# MS-PS3.net
KiCad netlist of a schematic drawn in EAGLE
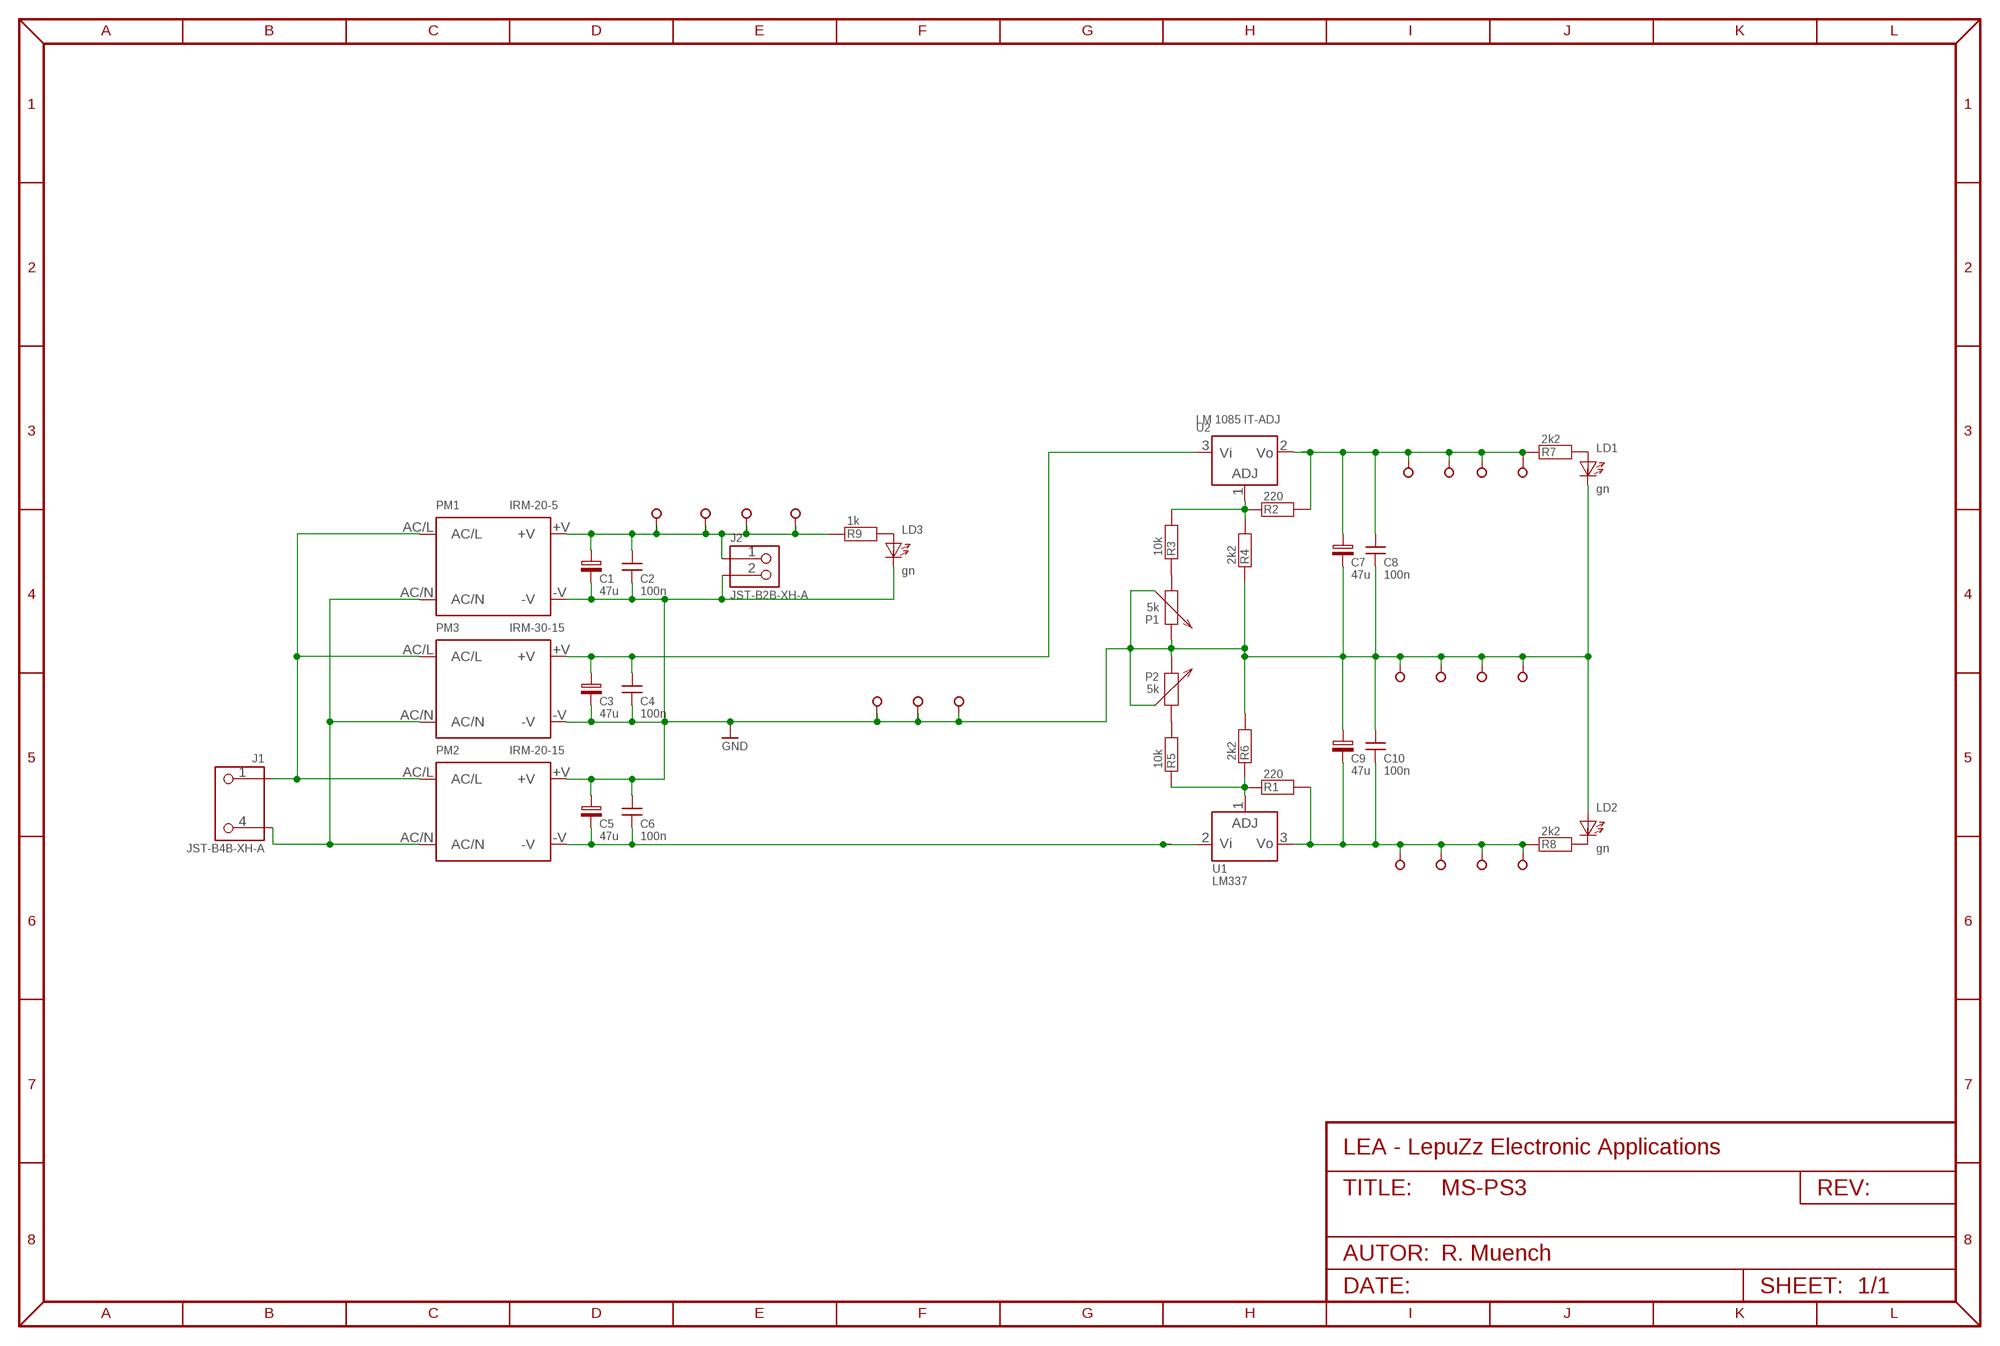
[diagram p0: schematic, sheet 1]

(export (version "E")
  (design (tool "Eeschema 10.0.6"))
  (components
    (comp (ref "C1")
      (value "47u")
      (footprint "eagle-import:ES2,5X6,3")
      (libsource (lib "eagle-import") (part "C-ELKO_2,5X6,3_R"))
    )
    (comp (ref "C2")
      (value "100n")
      (footprint "eagle-import:K5-2,5")
      (libsource (lib "eagle-import") (part "C_K_5X2.5"))
    )
    (comp (ref "C3")
      (value "47u")
      (footprint "eagle-import:ES2,5X6,3")
      (libsource (lib "eagle-import") (part "C-ELKO_2,5X6,3_R"))
    )
    (comp (ref "C4")
      (value "100n")
      (footprint "eagle-import:K5-2,5")
      (libsource (lib "eagle-import") (part "C_K_5X2.5"))
    )
    (comp (ref "C5")
      (value "47u")
      (footprint "eagle-import:ES2,5X6,3")
      (libsource (lib "eagle-import") (part "C-ELKO_2,5X6,3_R"))
    )
    (comp (ref "C6")
      (value "100n")
      (footprint "eagle-import:K5-2,5")
      (libsource (lib "eagle-import") (part "C_K_5X2.5"))
    )
    (comp (ref "C7")
      (value "47u")
      (footprint "eagle-import:ES2,5X6,3")
      (libsource (lib "eagle-import") (part "C-ELKO_2,5X6,3_R"))
    )
    (comp (ref "C8")
      (value "100n")
      (footprint "eagle-import:K5-2,5")
      (libsource (lib "eagle-import") (part "C_K_5X2.5"))
    )
    (comp (ref "C9")
      (value "47u")
      (footprint "eagle-import:ES2,5X6,3")
      (libsource (lib "eagle-import") (part "C-ELKO_2,5X6,3_R"))
    )
    (comp (ref "C10")
      (value "100n")
      (footprint "eagle-import:K5-2,5")
      (libsource (lib "eagle-import") (part "C_K_5X2.5"))
    )
    (comp (ref "J1")
      (value "JST-B4B-XH-A")
      (footprint "eagle-import:JST-B4B-XH-A-HV")
      (libsource (lib "eagle-import") (part "CON04"))
    )
    (comp (ref "J2")
      (value "JST-B2B-XH-A")
      (footprint "eagle-import:JST-B2B-XH-A")
      (libsource (lib "eagle-import") (part "CON02XH-B2B"))
    )
    (comp (ref "J3")
      (value "FLACHSTECKER-6,35")
      (footprint "eagle-import:FLACHSTECKER-6,35")
      (libsource (lib "eagle-import") (part "FLACHSTECKER-6,35"))
    )
    (comp (ref "J4")
      (value "FLACHSTECKER-6,35")
      (footprint "eagle-import:FLACHSTECKER-6,35")
      (libsource (lib "eagle-import") (part "FLACHSTECKER-6,35"))
    )
    (comp (ref "J5")
      (value "FLACHSTECKER-6,35")
      (footprint "eagle-import:FLACHSTECKER-6,35")
      (libsource (lib "eagle-import") (part "FLACHSTECKER-6,35"))
    )
    (comp (ref "J6")
      (value "FLACHSTECKER-6,35")
      (footprint "eagle-import:FLACHSTECKER-6,35")
      (libsource (lib "eagle-import") (part "FLACHSTECKER-6,35"))
    )
    (comp (ref "J7")
      (value "FLACHSTECKER-6,35")
      (footprint "eagle-import:FLACHSTECKER-6,35")
      (libsource (lib "eagle-import") (part "FLACHSTECKER-6,35"))
    )
    (comp (ref "J8")
      (value "FLACHSTECKER-6,35")
      (footprint "eagle-import:FLACHSTECKER-6,35")
      (libsource (lib "eagle-import") (part "FLACHSTECKER-6,35"))
    )
    (comp (ref "J9")
      (value "FLACHSTECKER-6,35")
      (footprint "eagle-import:FLACHSTECKER-6,35")
      (libsource (lib "eagle-import") (part "FLACHSTECKER-6,35"))
    )
    (comp (ref "J10")
      (value "FLACHSTECKER-6,35")
      (footprint "eagle-import:FLACHSTECKER-6,35")
      (libsource (lib "eagle-import") (part "FLACHSTECKER-6,35"))
    )
    (comp (ref "J11")
      (value "FLACHSTECKER-6,35")
      (footprint "eagle-import:FLACHSTECKER-6,35")
      (libsource (lib "eagle-import") (part "FLACHSTECKER-6,35"))
    )
    (comp (ref "J12")
      (value "FLACHSTECKER-6,35")
      (footprint "eagle-import:FLACHSTECKER-6,35")
      (libsource (lib "eagle-import") (part "FLACHSTECKER-6,35"))
    )
    (comp (ref "J13")
      (value "FLACHSTECKER-6,35")
      (footprint "eagle-import:FLACHSTECKER-6,35")
      (libsource (lib "eagle-import") (part "FLACHSTECKER-6,35"))
    )
    (comp (ref "J14")
      (value "FLACHSTECKER-6,35")
      (footprint "eagle-import:FLACHSTECKER-6,35")
      (libsource (lib "eagle-import") (part "FLACHSTECKER-6,35"))
    )
    (comp (ref "J15")
      (value "FLACHSTECKER-6,35")
      (footprint "eagle-import:FLACHSTECKER-6,35")
      (libsource (lib "eagle-import") (part "FLACHSTECKER-6,35"))
    )
    (comp (ref "J16")
      (value "FLACHSTECKER-6,35")
      (footprint "eagle-import:FLACHSTECKER-6,35")
      (libsource (lib "eagle-import") (part "FLACHSTECKER-6,35"))
    )
    (comp (ref "J17")
      (value "FLACHSTECKER-6,35")
      (footprint "eagle-import:FLACHSTECKER-6,35")
      (libsource (lib "eagle-import") (part "FLACHSTECKER-6,35"))
    )
    (comp (ref "J18")
      (value "FLACHSTECKER-6,35")
      (footprint "eagle-import:FLACHSTECKER-6,35")
      (libsource (lib "eagle-import") (part "FLACHSTECKER-6,35"))
    )
    (comp (ref "J19")
      (value "FLACHSTECKER-6,35")
      (footprint "eagle-import:FLACHSTECKER-6,35")
      (libsource (lib "eagle-import") (part "FLACHSTECKER-6,35"))
    )
    (comp (ref "J20")
      (value "FLACHSTECKER-6,35")
      (footprint "eagle-import:FLACHSTECKER-6,35")
      (libsource (lib "eagle-import") (part "FLACHSTECKER-6,35"))
    )
    (comp (ref "J21")
      (value "FLACHSTECKER-6,35")
      (footprint "eagle-import:FLACHSTECKER-6,35")
      (libsource (lib "eagle-import") (part "FLACHSTECKER-6,35"))
    )
    (comp (ref "LD1")
      (value "gn")
      (footprint "eagle-import:LED3")
      (libsource (lib "eagle-import") (part "LED3MM"))
    )
    (comp (ref "LD2")
      (value "gn")
      (footprint "eagle-import:LED3")
      (libsource (lib "eagle-import") (part "LED3MM"))
    )
    (comp (ref "LD3")
      (value "gn")
      (footprint "eagle-import:LED3")
      (libsource (lib "eagle-import") (part "LED3MM"))
    )
    (comp (ref "P1")
      (value "5k")
      (footprint "eagle-import:POT-25-64Y")
      (libsource (lib "eagle-import") (part "R-TRIM64Y"))
    )
    (comp (ref "P2")
      (value "5k")
      (footprint "eagle-import:POT-25-64Y")
      (libsource (lib "eagle-import") (part "R-TRIM64Y"))
    )
    (comp (ref "PM1")
      (value "IRM-20-5")
      (footprint "eagle-import:IRM-20")
      (libsource (lib "eagle-import") (part "IRM-XX20WATT"))
    )
    (comp (ref "PM2")
      (value "IRM-20-15")
      (footprint "eagle-import:IRM-20")
      (libsource (lib "eagle-import") (part "IRM-XX20WATT"))
    )
    (comp (ref "PM3")
      (value "IRM-30-15")
      (footprint "eagle-import:IRM-30")
      (libsource (lib "eagle-import") (part "IRM-XX30WATT"))
    )
    (comp (ref "R1")
      (value "220")
      (footprint "eagle-import:R-7,5")
      (libsource (lib "eagle-import") (part "R_7.5_250"))
    )
    (comp (ref "R2")
      (value "220")
      (footprint "eagle-import:R-7,5")
      (libsource (lib "eagle-import") (part "R_7.5_250"))
    )
    (comp (ref "R3")
      (value "10k")
      (footprint "eagle-import:R-7,5")
      (libsource (lib "eagle-import") (part "R_7.5_250"))
    )
    (comp (ref "R4")
      (value "2k2")
      (footprint "eagle-import:R-7,5")
      (libsource (lib "eagle-import") (part "R_7.5_250"))
    )
    (comp (ref "R5")
      (value "10k")
      (footprint "eagle-import:R-7,5")
      (libsource (lib "eagle-import") (part "R_7.5_250"))
    )
    (comp (ref "R6")
      (value "2k2")
      (footprint "eagle-import:R-7,5")
      (libsource (lib "eagle-import") (part "R_7.5_250"))
    )
    (comp (ref "R7")
      (value "2k2")
      (footprint "eagle-import:R-7,5")
      (libsource (lib "eagle-import") (part "R_7.5_250"))
    )
    (comp (ref "R8")
      (value "2k2")
      (footprint "eagle-import:R-7,5")
      (libsource (lib "eagle-import") (part "R_7.5_250"))
    )
    (comp (ref "R9")
      (value "1k")
      (footprint "eagle-import:R-7,5")
      (libsource (lib "eagle-import") (part "R_7.5_250"))
    )
    (comp (ref "U$5")
      (value "SK65")
      (footprint "eagle-import:SK65-37,5")
      (libsource (lib "eagle-import") (part "SK65"))
    )
    (comp (ref "U$7")
      (value "SK65")
      (footprint "eagle-import:SK65-37,5")
      (libsource (lib "eagle-import") (part "SK65"))
    )
    (comp (ref "U1")
      (value "LM337")
      (footprint "eagle-import:TO-220N")
      (libsource (lib "eagle-import") (part "337TA"))
    )
    (comp (ref "U2")
      (value "LM 1085 IT-ADJ")
      (footprint "eagle-import:TO-220N")
      (libsource (lib "eagle-import") (part "317TN"))
    )
  )
  (nets
    (net (code "1") (name "GND") (class "Default")
      (node (ref "C1") (pin "2") (pinfunction "2_2") (pintype "passive"))
      (node (ref "C10") (pin "1") (pinfunction "1_1") (pintype "passive"))
      (node (ref "C2") (pin "2") (pinfunction "2_2") (pintype "passive"))
      (node (ref "C3") (pin "2") (pinfunction "2_2") (pintype "passive"))
      (node (ref "C4") (pin "2") (pinfunction "2_2") (pintype "passive"))
      (node (ref "C5") (pin "1") (pinfunction "1_1") (pintype "passive"))
      (node (ref "C6") (pin "1") (pinfunction "1_1") (pintype "passive"))
      (node (ref "C7") (pin "2") (pinfunction "2_2") (pintype "passive"))
      (node (ref "C8") (pin "2") (pinfunction "2_2") (pintype "passive"))
      (node (ref "C9") (pin "1") (pinfunction "1_1") (pintype "passive"))
      (node (ref "J13") (pin "P$1") (pinfunction "P$1_P$1") (pintype "bidirectional"))
      (node (ref "J13") (pin "P$2") (pinfunction "P$2_P$2") (pintype "bidirectional"))
      (node (ref "J14") (pin "P$1") (pinfunction "P$1_P$1") (pintype "bidirectional"))
      (node (ref "J14") (pin "P$2") (pinfunction "P$2_P$2") (pintype "bidirectional"))
      (node (ref "J15") (pin "P$1") (pinfunction "P$1_P$1") (pintype "bidirectional"))
      (node (ref "J15") (pin "P$2") (pinfunction "P$2_P$2") (pintype "bidirectional"))
      (node (ref "J16") (pin "P$1") (pinfunction "P$1_P$1") (pintype "bidirectional"))
      (node (ref "J16") (pin "P$2") (pinfunction "P$2_P$2") (pintype "bidirectional"))
      (node (ref "J2") (pin "2") (pinfunction "2_2") (pintype "passive"))
      (node (ref "J21") (pin "P$1") (pinfunction "P$1_P$1") (pintype "bidirectional"))
      (node (ref "J21") (pin "P$2") (pinfunction "P$2_P$2") (pintype "bidirectional"))
      (node (ref "J7") (pin "P$1") (pinfunction "P$1_P$1") (pintype "bidirectional"))
      (node (ref "J7") (pin "P$2") (pinfunction "P$2_P$2") (pintype "bidirectional"))
      (node (ref "J8") (pin "P$1") (pinfunction "P$1_P$1") (pintype "bidirectional"))
      (node (ref "J8") (pin "P$2") (pinfunction "P$2_P$2") (pintype "bidirectional"))
      (node (ref "LD1") (pin "K") (pinfunction "K_K") (pintype "passive"))
      (node (ref "LD2") (pin "A") (pinfunction "A_A") (pintype "passive"))
      (node (ref "LD3") (pin "K") (pinfunction "K_K") (pintype "passive"))
      (node (ref "P1") (pin "2") (pinfunction "2_2") (pintype "passive"))
      (node (ref "P1") (pin "3") (pinfunction "3_3") (pintype "passive"))
      (node (ref "P2") (pin "2") (pinfunction "2_2") (pintype "passive"))
      (node (ref "P2") (pin "3") (pinfunction "3_3") (pintype "passive"))
      (node (ref "PM1") (pin "-V") (pinfunction "-V_-V") (pintype "passive"))
      (node (ref "PM2") (pin "+V") (pinfunction "+V_+V") (pintype "passive"))
      (node (ref "PM3") (pin "-V") (pinfunction "-V_-V") (pintype "passive"))
      (node (ref "R4") (pin "1") (pinfunction "1_1") (pintype "passive"))
      (node (ref "R6") (pin "2") (pinfunction "2_2") (pintype "passive"))
    )
    (net (code "2") (name "Net-(C1-Pad1)") (class "Default")
      (node (ref "C1") (pin "1") (pinfunction "1_1") (pintype "passive"))
      (node (ref "C2") (pin "1") (pinfunction "1_1") (pintype "passive"))
      (node (ref "J2") (pin "1") (pinfunction "1_1") (pintype "passive"))
      (node (ref "J3") (pin "P$1") (pinfunction "P$1_P$1") (pintype "bidirectional"))
      (node (ref "J3") (pin "P$2") (pinfunction "P$2_P$2") (pintype "bidirectional"))
      (node (ref "J4") (pin "P$1") (pinfunction "P$1_P$1") (pintype "bidirectional"))
      (node (ref "J4") (pin "P$2") (pinfunction "P$2_P$2") (pintype "bidirectional"))
      (node (ref "J5") (pin "P$1") (pinfunction "P$1_P$1") (pintype "bidirectional"))
      (node (ref "J5") (pin "P$2") (pinfunction "P$2_P$2") (pintype "bidirectional"))
      (node (ref "J6") (pin "P$1") (pinfunction "P$1_P$1") (pintype "bidirectional"))
      (node (ref "J6") (pin "P$2") (pinfunction "P$2_P$2") (pintype "bidirectional"))
      (node (ref "PM1") (pin "+V") (pinfunction "+V_+V") (pintype "passive"))
      (node (ref "R9") (pin "1") (pinfunction "1_1") (pintype "passive"))
    )
    (net (code "3") (name "Net-(J1-Pad1)") (class "Default")
      (node (ref "J1") (pin "1") (pinfunction "1_1") (pintype "passive"))
      (node (ref "PM1") (pin "AC/L") (pinfunction "AC/L_AC/L") (pintype "passive"))
      (node (ref "PM2") (pin "AC/L") (pinfunction "AC/L_AC/L") (pintype "passive"))
      (node (ref "PM3") (pin "AC/L") (pinfunction "AC/L_AC/L") (pintype "passive"))
    )
    (net (code "4") (name "Net-(J1-Pad4)") (class "Default")
      (node (ref "J1") (pin "4") (pinfunction "4_4") (pintype "passive"))
      (node (ref "PM1") (pin "AC/N") (pinfunction "AC/N_AC/N") (pintype "passive"))
      (node (ref "PM2") (pin "AC/N") (pinfunction "AC/N_AC/N") (pintype "passive"))
      (node (ref "PM3") (pin "AC/N") (pinfunction "AC/N_AC/N") (pintype "passive"))
    )
    (net (code "5") (name "Net-(LD1-PadA)") (class "Default")
      (node (ref "LD1") (pin "A") (pinfunction "A_A") (pintype "passive"))
      (node (ref "R7") (pin "2") (pinfunction "2_2") (pintype "passive"))
    )
    (net (code "6") (name "Net-(LD2-PadK)") (class "Default")
      (node (ref "LD2") (pin "K") (pinfunction "K_K") (pintype "passive"))
      (node (ref "R8") (pin "2") (pinfunction "2_2") (pintype "passive"))
    )
    (net (code "7") (name "Net-(LD3-PadA)") (class "Default")
      (node (ref "LD3") (pin "A") (pinfunction "A_A") (pintype "passive"))
      (node (ref "R9") (pin "2") (pinfunction "2_2") (pintype "passive"))
    )
    (net (code "8") (name "Net-(P1-Pad1)") (class "Default")
      (node (ref "P1") (pin "1") (pinfunction "1_1") (pintype "passive"))
      (node (ref "R3") (pin "1") (pinfunction "1_1") (pintype "passive"))
    )
    (net (code "9") (name "Net-(P2-Pad1)") (class "Default")
      (node (ref "P2") (pin "1") (pinfunction "1_1") (pintype "passive"))
      (node (ref "R5") (pin "2") (pinfunction "2_2") (pintype "passive"))
    )
    (net (code "10") (name "Net-(U1-ADJ)") (class "Default")
      (node (ref "R1") (pin "1") (pinfunction "1_1") (pintype "passive"))
      (node (ref "R5") (pin "1") (pinfunction "1_1") (pintype "passive"))
      (node (ref "R6") (pin "1") (pinfunction "1_1") (pintype "passive"))
      (node (ref "U1") (pin "1") (pinfunction "ADJ_1") (pintype "input"))
    )
    (net (code "11") (name "Net-(U1-VI)") (class "Default")
      (node (ref "C5") (pin "2") (pinfunction "2_2") (pintype "passive"))
      (node (ref "C6") (pin "2") (pinfunction "2_2") (pintype "passive"))
      (node (ref "PM2") (pin "-V") (pinfunction "-V_-V") (pintype "passive"))
      (node (ref "U$5") (pin "P$1") (pinfunction "P$1_P$1") (pintype "bidirectional"))
      (node (ref "U$5") (pin "P$2") (pinfunction "P$2_P$2") (pintype "bidirectional"))
      (node (ref "U1") (pin "2") (pinfunction "VI_2") (pintype "input"))
    )
    (net (code "12") (name "Net-(U1-VO)") (class "Default")
      (node (ref "C10") (pin "2") (pinfunction "2_2") (pintype "passive"))
      (node (ref "C9") (pin "2") (pinfunction "2_2") (pintype "passive"))
      (node (ref "J17") (pin "P$1") (pinfunction "P$1_P$1") (pintype "bidirectional"))
      (node (ref "J17") (pin "P$2") (pinfunction "P$2_P$2") (pintype "bidirectional"))
      (node (ref "J18") (pin "P$1") (pinfunction "P$1_P$1") (pintype "bidirectional"))
      (node (ref "J18") (pin "P$2") (pinfunction "P$2_P$2") (pintype "bidirectional"))
      (node (ref "J19") (pin "P$1") (pinfunction "P$1_P$1") (pintype "bidirectional"))
      (node (ref "J19") (pin "P$2") (pinfunction "P$2_P$2") (pintype "bidirectional"))
      (node (ref "J20") (pin "P$1") (pinfunction "P$1_P$1") (pintype "bidirectional"))
      (node (ref "J20") (pin "P$2") (pinfunction "P$2_P$2") (pintype "bidirectional"))
      (node (ref "R1") (pin "2") (pinfunction "2_2") (pintype "passive"))
      (node (ref "R8") (pin "1") (pinfunction "1_1") (pintype "passive"))
      (node (ref "U1") (pin "3") (pinfunction "VO_3") (pintype "output"))
    )
    (net (code "13") (name "Net-(U2-ADJ)") (class "Default")
      (node (ref "R2") (pin "1") (pinfunction "1_1") (pintype "passive"))
      (node (ref "R3") (pin "2") (pinfunction "2_2") (pintype "passive"))
      (node (ref "R4") (pin "2") (pinfunction "2_2") (pintype "passive"))
      (node (ref "U2") (pin "1") (pinfunction "ADJ_1") (pintype "input"))
    )
    (net (code "14") (name "Net-(U2-VI)") (class "Default")
      (node (ref "C3") (pin "1") (pinfunction "1_1") (pintype "passive"))
      (node (ref "C4") (pin "1") (pinfunction "1_1") (pintype "passive"))
      (node (ref "PM3") (pin "+V") (pinfunction "+V_+V") (pintype "passive"))
      (node (ref "U2") (pin "3") (pinfunction "VI_3") (pintype "input"))
    )
    (net (code "15") (name "Net-(U2-VO)") (class "Default")
      (node (ref "C7") (pin "1") (pinfunction "1_1") (pintype "passive"))
      (node (ref "C8") (pin "1") (pinfunction "1_1") (pintype "passive"))
      (node (ref "J10") (pin "P$1") (pinfunction "P$1_P$1") (pintype "bidirectional"))
      (node (ref "J10") (pin "P$2") (pinfunction "P$2_P$2") (pintype "bidirectional"))
      (node (ref "J11") (pin "P$1") (pinfunction "P$1_P$1") (pintype "bidirectional"))
      (node (ref "J11") (pin "P$2") (pinfunction "P$2_P$2") (pintype "bidirectional"))
      (node (ref "J12") (pin "P$1") (pinfunction "P$1_P$1") (pintype "bidirectional"))
      (node (ref "J9") (pin "P$1") (pinfunction "P$1_P$1") (pintype "bidirectional"))
      (node (ref "J9") (pin "P$2") (pinfunction "P$2_P$2") (pintype "bidirectional"))
      (node (ref "R2") (pin "2") (pinfunction "2_2") (pintype "passive"))
      (node (ref "R7") (pin "1") (pinfunction "1_1") (pintype "passive"))
      (node (ref "U$7") (pin "P$1") (pinfunction "P$1_P$1") (pintype "bidirectional"))
      (node (ref "U$7") (pin "P$2") (pinfunction "P$2_P$2") (pintype "bidirectional"))
      (node (ref "U2") (pin "2") (pinfunction "VO_2") (pintype "passive"))
    )
    (net (code "16") (name "unconnected-(J12-PadP$2)") (class "Default")
      (node (ref "J12") (pin "P$2") (pinfunction "P$2_P$2") (pintype "bidirectional"))
    )
  )
)
